# individual-board.net
KiCad netlist of a schematic drawn in EAGLE
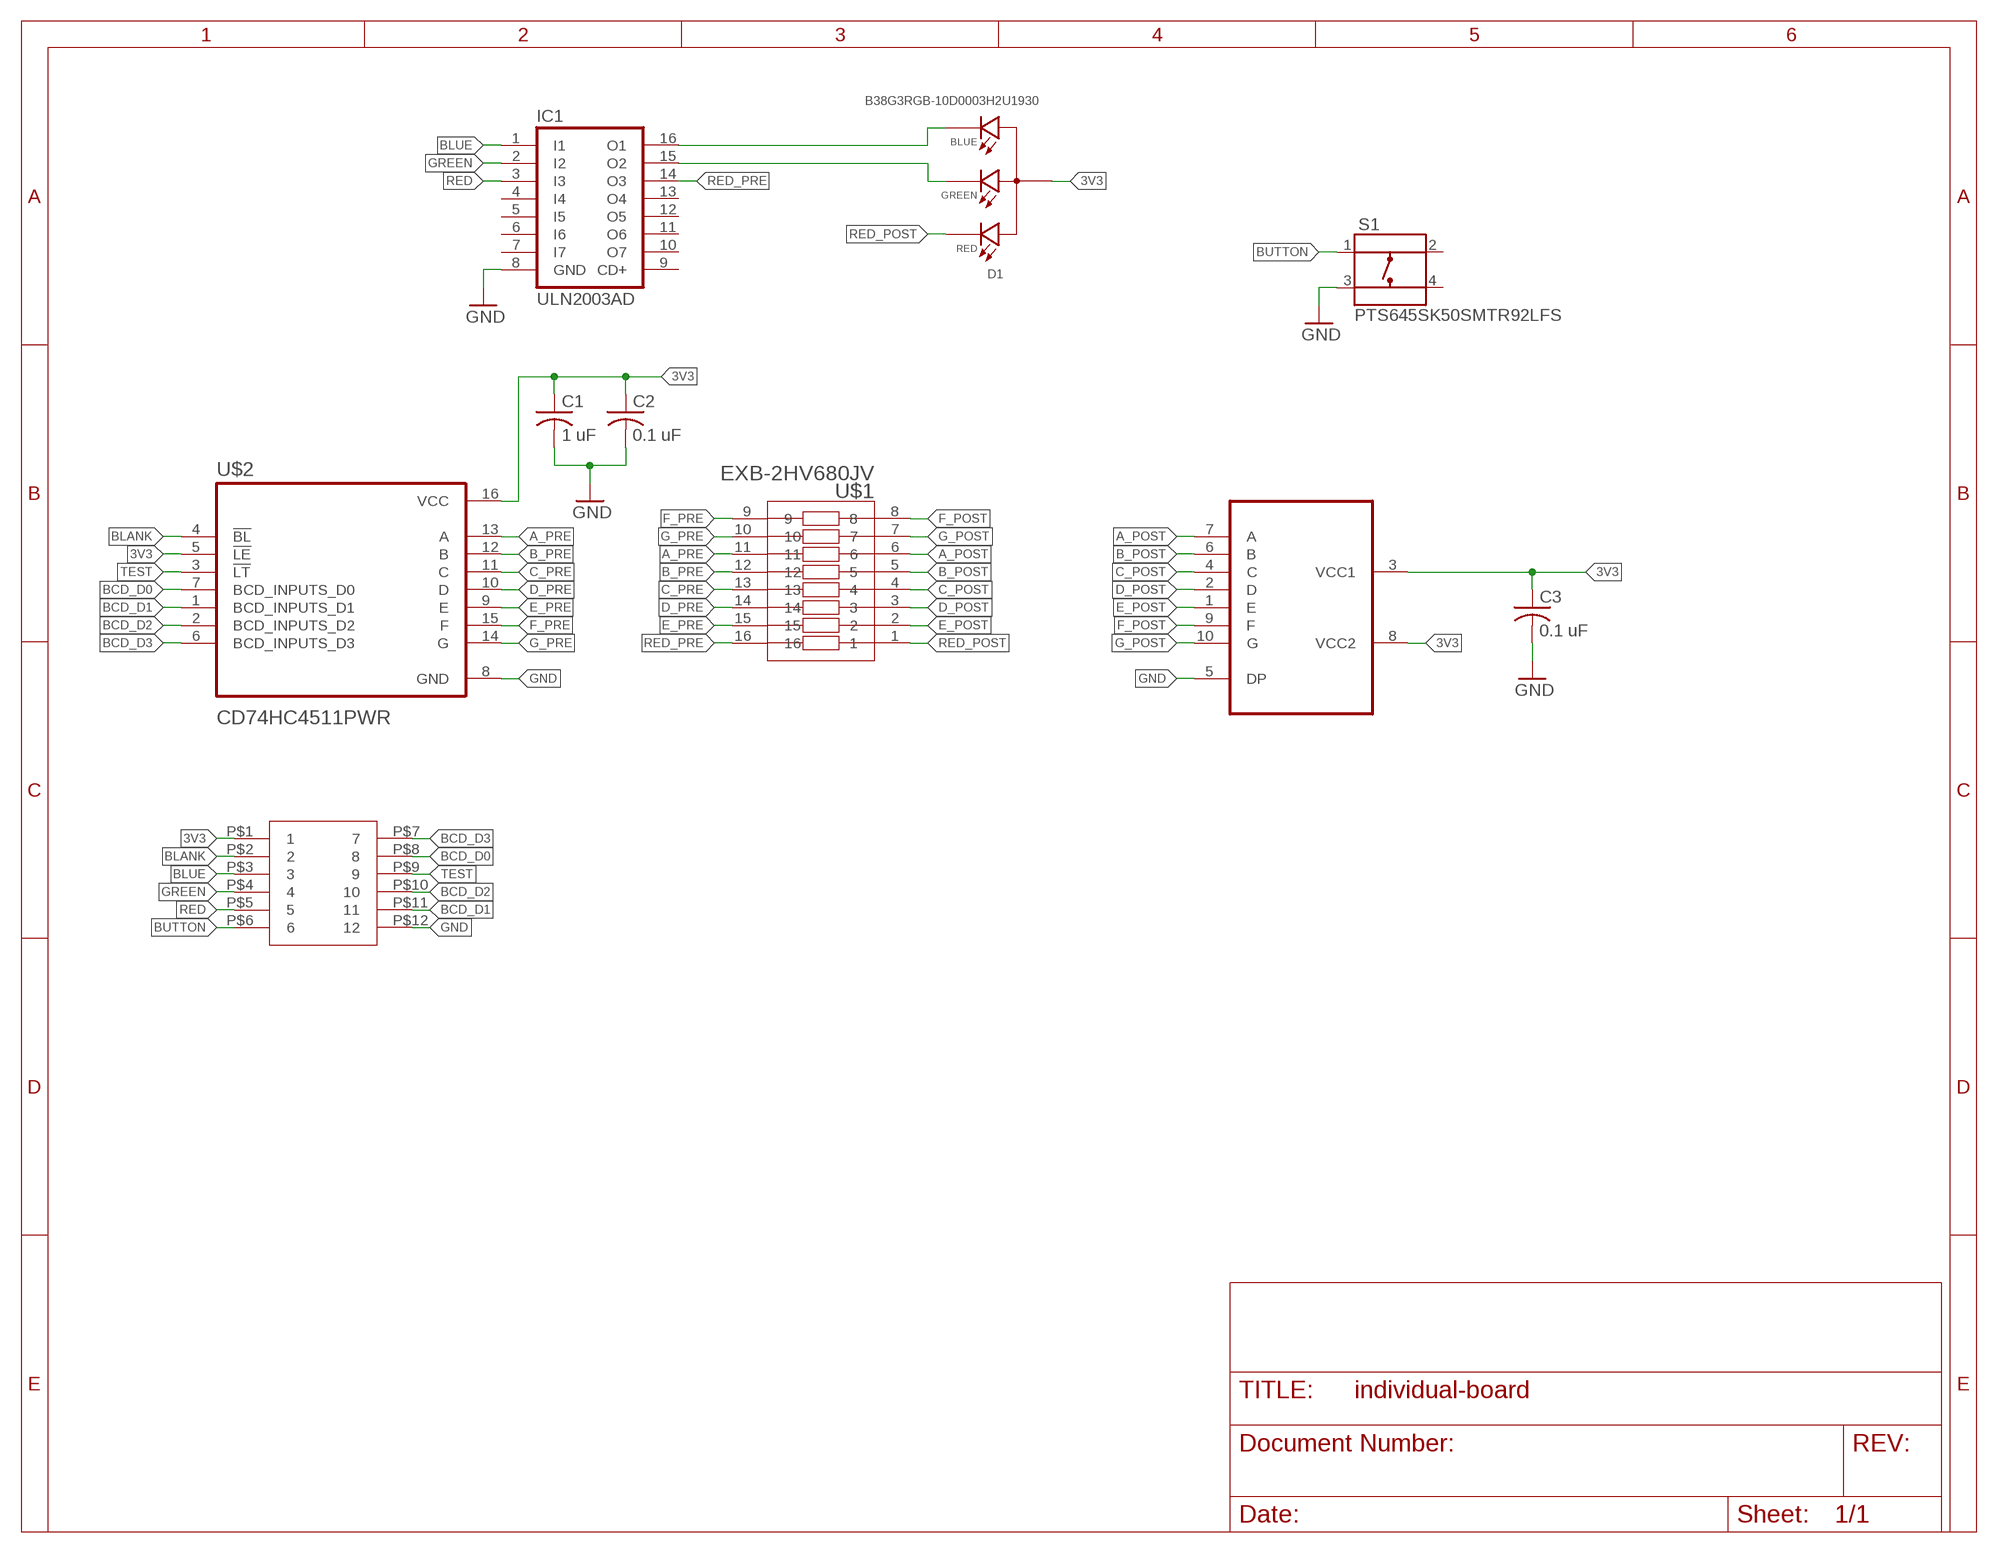
[diagram p0: schematic, sheet 1]

(export (version "E")
  (design (tool "Eeschema 10.0.6"))
  (components
    (comp (ref "C1")
      (value "1 uF")
      (footprint "eagle-import:C0603")
      (libsource (lib "eagle-import") (part "C-USC0603"))
    )
    (comp (ref "C2")
      (value "0.1 uF")
      (footprint "eagle-import:C0603")
      (libsource (lib "eagle-import") (part "C-USC0603"))
    )
    (comp (ref "C3")
      (value "0.1 uF")
      (footprint "eagle-import:C0603")
      (libsource (lib "eagle-import") (part "C-USC0603"))
    )
    (comp (ref "D1")
      (value "B38G3RGB-10D0003H2U1930")
      (footprint "eagle-import:LED_B38G3RGB-10D0003H2U1930")
      (fields
        (field (name "DIGI-KEY_PART_NUMBER") "3147-B38G3RGB-10D0003H2U1930TR-ND")
        (field (name "MF") "Harvatek Corporation")
      )
      (libsource (lib "eagle-import") (part "B38G3RGB-10D0003H2U1930"))
    )
    (comp (ref "IC1")
      (value "ULN2003AD")
      (footprint "eagle-import:SO16")
      (libsource (lib "eagle-import") (part "ULN2003AD"))
    )
    (comp (ref "S1")
      (value "PTS645SK50SMTR92LFS")
      (footprint "eagle-import:SW_PTS645SK50SMTR92LFS")
      (fields (field (name "DIGI-KEY_PART_NUMBER") "CKN9087TR-ND") (field (name "MF") "C&K"))
      (libsource (lib "eagle-import") (part "PTS645SK50SMTR92LFS"))
    )
    (comp (ref "U$1")
      (value "EXB-2HV680JV")
      (footprint "eagle-import:2HV")
      (fields
        (field (name "DIGI-KEY_PART_NUMBER") "Y1101TR-ND")
        (field (name "MF") "Panasonic Electronic")
        (field (name "MP") "EXB-2HV101JV")
      )
      (libsource (lib "eagle-import") (part "EXB-2HV101JV"))
    )
    (comp (ref "U$2")
      (value "CD74HC4511PWR")
      (footprint "eagle-import:CD74HC4511PWR")
      (libsource (lib "eagle-import") (part "CD74HC4511PWR"))
    )
    (comp (ref "U$3")
      (value "INND-SS30RAB")
      (footprint "eagle-import:INND-SS30RAB")
      (libsource (lib "eagle-import") (part "INND-SS30RAB"))
    )
    (comp (ref "U$4")
      (value "2X6-EDGE-CONNECTOR")
      (footprint "eagle-import:2X6-EDGE-CONNECTOR")
      (libsource (lib "eagle-import") (part "2X6-EDGE-CONNECTOR"))
    )
  )
  (nets
    (net (code "1") (name "3V3") (class "Default")
      (node (ref "C1") (pin "1") (pinfunction "1_1") (pintype "passive"))
      (node (ref "C2") (pin "1") (pinfunction "1_1") (pintype "passive"))
      (node (ref "C3") (pin "1") (pinfunction "1_1") (pintype "passive"))
      (node (ref "D1") (pin "3") (pinfunction "A_3") (pintype "passive"))
      (node (ref "U$2") (pin "16") (pinfunction "VCC_16") (pintype "power_in"))
      (node (ref "U$2") (pin "5") (pinfunction "~{LE}_5") (pintype "input"))
      (node (ref "U$3") (pin "3") (pinfunction "VCC1_3") (pintype "bidirectional"))
      (node (ref "U$3") (pin "8") (pinfunction "VCC2_8") (pintype "bidirectional"))
      (node (ref "U$4") (pin "P$1") (pinfunction "1_P$1") (pintype "bidirectional"))
    )
    (net (code "2") (name "A_POST") (class "Default")
      (node (ref "U$1") (pin "6") (pinfunction "6_6") (pintype "bidirectional"))
      (node (ref "U$3") (pin "7") (pinfunction "A_7") (pintype "bidirectional"))
    )
    (net (code "3") (name "A_PRE") (class "Default")
      (node (ref "U$1") (pin "11") (pinfunction "11_11") (pintype "bidirectional"))
      (node (ref "U$2") (pin "13") (pinfunction "A_13") (pintype "output"))
    )
    (net (code "4") (name "BCD_D0") (class "Default")
      (node (ref "U$2") (pin "7") (pinfunction "BCD_INPUTS_D0_7") (pintype "input"))
      (node (ref "U$4") (pin "P$8") (pinfunction "8_P$8") (pintype "bidirectional"))
    )
    (net (code "5") (name "BCD_D1") (class "Default")
      (node (ref "U$2") (pin "1") (pinfunction "BCD_INPUTS_D1_1") (pintype "input"))
      (node (ref "U$4") (pin "P$11") (pinfunction "11_P$11") (pintype "bidirectional"))
    )
    (net (code "6") (name "BCD_D2") (class "Default")
      (node (ref "U$2") (pin "2") (pinfunction "BCD_INPUTS_D2_2") (pintype "input"))
      (node (ref "U$4") (pin "P$10") (pinfunction "10_P$10") (pintype "bidirectional"))
    )
    (net (code "7") (name "BCD_D3") (class "Default")
      (node (ref "U$2") (pin "6") (pinfunction "BCD_INPUTS_D3_6") (pintype "input"))
      (node (ref "U$4") (pin "P$7") (pinfunction "7_P$7") (pintype "bidirectional"))
    )
    (net (code "8") (name "BLANK") (class "Default")
      (node (ref "U$2") (pin "4") (pinfunction "~{BL}_4") (pintype "input"))
      (node (ref "U$4") (pin "P$2") (pinfunction "2_P$2") (pintype "bidirectional"))
    )
    (net (code "9") (name "BLUE") (class "Default")
      (node (ref "IC1") (pin "1") (pinfunction "I1_1") (pintype "input"))
      (node (ref "U$4") (pin "P$3") (pinfunction "3_P$3") (pintype "bidirectional"))
    )
    (net (code "10") (name "BUTTON") (class "Default")
      (node (ref "S1") (pin "1") (pinfunction "1_1") (pintype "passive"))
      (node (ref "U$4") (pin "P$6") (pinfunction "6_P$6") (pintype "bidirectional"))
    )
    (net (code "11") (name "B_POST") (class "Default")
      (node (ref "U$1") (pin "5") (pinfunction "5_5") (pintype "bidirectional"))
      (node (ref "U$3") (pin "6") (pinfunction "B_6") (pintype "bidirectional"))
    )
    (net (code "12") (name "B_PRE") (class "Default")
      (node (ref "U$1") (pin "12") (pinfunction "12_12") (pintype "bidirectional"))
      (node (ref "U$2") (pin "12") (pinfunction "B_12") (pintype "output"))
    )
    (net (code "13") (name "C_POST") (class "Default")
      (node (ref "U$1") (pin "4") (pinfunction "4_4") (pintype "bidirectional"))
      (node (ref "U$3") (pin "4") (pinfunction "C_4") (pintype "bidirectional"))
    )
    (net (code "14") (name "C_PRE") (class "Default")
      (node (ref "U$1") (pin "13") (pinfunction "13_13") (pintype "bidirectional"))
      (node (ref "U$2") (pin "11") (pinfunction "C_11") (pintype "output"))
    )
    (net (code "15") (name "D_POST") (class "Default")
      (node (ref "U$1") (pin "3") (pinfunction "3_3") (pintype "bidirectional"))
      (node (ref "U$3") (pin "2") (pinfunction "D_2") (pintype "bidirectional"))
    )
    (net (code "16") (name "D_PRE") (class "Default")
      (node (ref "U$1") (pin "14") (pinfunction "14_14") (pintype "bidirectional"))
      (node (ref "U$2") (pin "10") (pinfunction "D_10") (pintype "output"))
    )
    (net (code "17") (name "E_POST") (class "Default")
      (node (ref "U$1") (pin "2") (pinfunction "2_2") (pintype "bidirectional"))
      (node (ref "U$3") (pin "1") (pinfunction "E_1") (pintype "bidirectional"))
    )
    (net (code "18") (name "E_PRE") (class "Default")
      (node (ref "U$1") (pin "15") (pinfunction "15_15") (pintype "bidirectional"))
      (node (ref "U$2") (pin "9") (pinfunction "E_9") (pintype "output"))
    )
    (net (code "19") (name "F_POST") (class "Default")
      (node (ref "U$1") (pin "8") (pinfunction "8_8") (pintype "bidirectional"))
      (node (ref "U$3") (pin "9") (pinfunction "F_9") (pintype "bidirectional"))
    )
    (net (code "20") (name "F_PRE") (class "Default")
      (node (ref "U$1") (pin "9") (pinfunction "9_9") (pintype "bidirectional"))
      (node (ref "U$2") (pin "15") (pinfunction "F_15") (pintype "output"))
    )
    (net (code "21") (name "GND") (class "Default")
      (node (ref "C1") (pin "2") (pinfunction "2_2") (pintype "passive"))
      (node (ref "C2") (pin "2") (pinfunction "2_2") (pintype "passive"))
      (node (ref "C3") (pin "2") (pinfunction "2_2") (pintype "passive"))
      (node (ref "IC1") (pin "8") (pinfunction "GND_8") (pintype "power_in"))
      (node (ref "S1") (pin "3") (pinfunction "3_3") (pintype "passive"))
      (node (ref "U$2") (pin "8") (pinfunction "GND_8") (pintype "power_in"))
      (node (ref "U$3") (pin "5") (pinfunction "DP_5") (pintype "bidirectional"))
      (node (ref "U$4") (pin "P$12") (pinfunction "12_P$12") (pintype "bidirectional"))
    )
    (net (code "22") (name "GREEN") (class "Default")
      (node (ref "IC1") (pin "2") (pinfunction "I2_2") (pintype "input"))
      (node (ref "U$4") (pin "P$4") (pinfunction "4_P$4") (pintype "bidirectional"))
    )
    (net (code "23") (name "G_POST") (class "Default")
      (node (ref "U$1") (pin "7") (pinfunction "7_7") (pintype "bidirectional"))
      (node (ref "U$3") (pin "10") (pinfunction "G_10") (pintype "bidirectional"))
    )
    (net (code "24") (name "G_PRE") (class "Default")
      (node (ref "U$1") (pin "10") (pinfunction "10_10") (pintype "bidirectional"))
      (node (ref "U$2") (pin "14") (pinfunction "G_14") (pintype "output"))
    )
    (net (code "25") (name "Net-(D1-B_C)") (class "Default")
      (node (ref "D1") (pin "2") (pinfunction "B_C_2") (pintype "passive"))
      (node (ref "IC1") (pin "16") (pinfunction "O1_16") (pintype "open_collector"))
    )
    (net (code "26") (name "Net-(D1-G_C)") (class "Default")
      (node (ref "D1") (pin "1") (pinfunction "G_C_1") (pintype "passive"))
      (node (ref "IC1") (pin "15") (pinfunction "O2_15") (pintype "open_collector"))
    )
    (net (code "27") (name "RED") (class "Default")
      (node (ref "IC1") (pin "3") (pinfunction "I3_3") (pintype "input"))
      (node (ref "U$4") (pin "P$5") (pinfunction "5_P$5") (pintype "bidirectional"))
    )
    (net (code "28") (name "RED_POST") (class "Default")
      (node (ref "D1") (pin "4") (pinfunction "R_C_4") (pintype "passive"))
      (node (ref "U$1") (pin "1") (pinfunction "1_1") (pintype "bidirectional"))
    )
    (net (code "29") (name "RED_PRE") (class "Default")
      (node (ref "IC1") (pin "14") (pinfunction "O3_14") (pintype "open_collector"))
      (node (ref "U$1") (pin "16") (pinfunction "16_16") (pintype "bidirectional"))
    )
    (net (code "30") (name "TEST") (class "Default")
      (node (ref "U$2") (pin "3") (pinfunction "~{LT}_3") (pintype "input"))
      (node (ref "U$4") (pin "P$9") (pinfunction "9_P$9") (pintype "bidirectional"))
    )
    (net (code "31") (name "unconnected-(IC1-CD+-Pad9)") (class "Default")
      (node (ref "IC1") (pin "9") (pinfunction "CD+_9") (pintype "passive"))
    )
    (net (code "32") (name "unconnected-(IC1-I4-Pad4)") (class "Default")
      (node (ref "IC1") (pin "4") (pinfunction "I4_4") (pintype "input"))
    )
    (net (code "33") (name "unconnected-(IC1-I5-Pad5)") (class "Default")
      (node (ref "IC1") (pin "5") (pinfunction "I5_5") (pintype "input"))
    )
    (net (code "34") (name "unconnected-(IC1-I6-Pad6)") (class "Default")
      (node (ref "IC1") (pin "6") (pinfunction "I6_6") (pintype "input"))
    )
    (net (code "35") (name "unconnected-(IC1-I7-Pad7)") (class "Default")
      (node (ref "IC1") (pin "7") (pinfunction "I7_7") (pintype "input"))
    )
    (net (code "36") (name "unconnected-(IC1-O4-Pad13)") (class "Default")
      (node (ref "IC1") (pin "13") (pinfunction "O4_13") (pintype "open_collector"))
    )
    (net (code "37") (name "unconnected-(IC1-O5-Pad12)") (class "Default")
      (node (ref "IC1") (pin "12") (pinfunction "O5_12") (pintype "open_collector"))
    )
    (net (code "38") (name "unconnected-(IC1-O6-Pad11)") (class "Default")
      (node (ref "IC1") (pin "11") (pinfunction "O6_11") (pintype "open_collector"))
    )
    (net (code "39") (name "unconnected-(IC1-O7-Pad10)") (class "Default")
      (node (ref "IC1") (pin "10") (pinfunction "O7_10") (pintype "open_collector"))
    )
    (net (code "40") (name "unconnected-(S1-Pad2)") (class "Default")
      (node (ref "S1") (pin "2") (pinfunction "2_2") (pintype "passive"))
    )
    (net (code "41") (name "unconnected-(S1-Pad4)") (class "Default")
      (node (ref "S1") (pin "4") (pinfunction "4_4") (pintype "passive"))
    )
  )
)
